# Opto_AQY280SX.net
KiCad netlist of a schematic drawn in Altium Designer
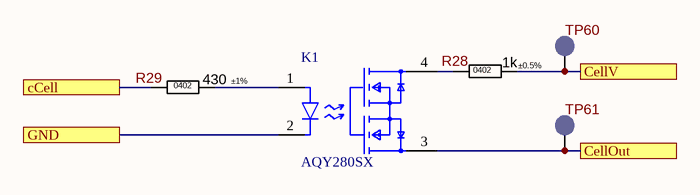
[diagram p0: Opto_AQY280SX.SchDoc]

(export (version "E")
  (design (tool "Eeschema 10.0.6"))
  (components
    (comp (ref "K1")
      (value "AQY280SX")
      (footprint "FP-AQY280SX-MFG")
      (description "AQY280SX AQY Photomos Series 120 mA 350 V 25 Ohm SMT 1 Channel Solid State Relay -SOP-4")
      (libsource (lib "EL.XXX.T01") (part "CMP-00287-00695349-1"))
    )
    (comp (ref "R28")
      (value "1k")
      (footprint "R_ANY_CHIP_0402_MED")
      (description "1 kOhms ±0.5% 1/16W 0402 Thick Film Resistor")
      (fields
        (field (name "TOLERANCE") "±0.5%")
        (field (name "PACKAGE") "0402")
        (field (name "PART NUMBER") "RC0402DR-071KL")
        (field (name "MANUFACTURER") "Yageo")
      )
      (libsource (lib "EL.XXX.T01") (part "RC0402DR-071KL"))
    )
    (comp (ref "R29")
      (value "430")
      (footprint "R_ANY_CHIP_0402_MED")
      (description "430 Ohms ±1% 1/16W 0402 Thick Film Resistor")
      (fields
        (field (name "TOLERANCE") "±1%")
        (field (name "PACKAGE") "0402")
        (field (name "PART NUMBER") "RC0402FR-07430RL")
        (field (name "MANUFACTURER") "Yageo")
      )
      (libsource (lib "EL.XXX.T01") (part "RC0402FR-07430RL"))
    )
    (comp (ref "TP60")
      (value "LED_LINK")
      (footprint "TP_SMD_2mm")
      (description "Test Point SMD Pad 1.0mm/1.5mm/2mm")
      (fields (field (name "PART NUMBER") "TP-PAD-SMD"))
      (libsource (lib "EL.XXX.T01") (part "TP-PAD-SMD"))
    )
    (comp (ref "TP61")
      (value "LED_LINK")
      (footprint "TP_SMD_2mm")
      (description "Test Point SMD Pad 1.0mm/1.5mm/2mm")
      (fields (field (name "PART NUMBER") "TP-PAD-SMD"))
      (libsource (lib "EL.XXX.T01") (part "TP-PAD-SMD"))
    )
  )
  (nets
    (net (code "1") (name "/CellOut") (class "Default")
      (node (ref "K1") (pin "3") (pinfunction "1_DRAIN_3") (pintype "passive"))
      (node (ref "TP61") (pin "1") (pintype "passive"))
    )
    (net (code "2") (name "/CellV") (class "Default")
      (node (ref "R28") (pin "2") (pintype "passive"))
      (node (ref "TP60") (pin "1") (pintype "passive"))
    )
    (net (code "3") (name "/GND") (class "Default")
      (node (ref "K1") (pin "2") (pinfunction "C_2") (pintype "passive"))
    )
    (net (code "4") (name "/cCell") (class "Default") (node (ref "R29") (pin "1") (pintype "passive")))
    (net (code "5") (name "Net-(K1-2_DRAIN)") (class "Default")
      (node (ref "K1") (pin "4") (pinfunction "2_DRAIN_4") (pintype "passive"))
      (node (ref "R28") (pin "1") (pintype "passive"))
    )
    (net (code "6") (name "Net-(K1-A)") (class "Default")
      (node (ref "K1") (pin "1") (pinfunction "A_1") (pintype "passive"))
      (node (ref "R29") (pin "2") (pintype "passive"))
    )
  )
)
